# teensy.net
KiCad netlist of a schematic drawn in EAGLE
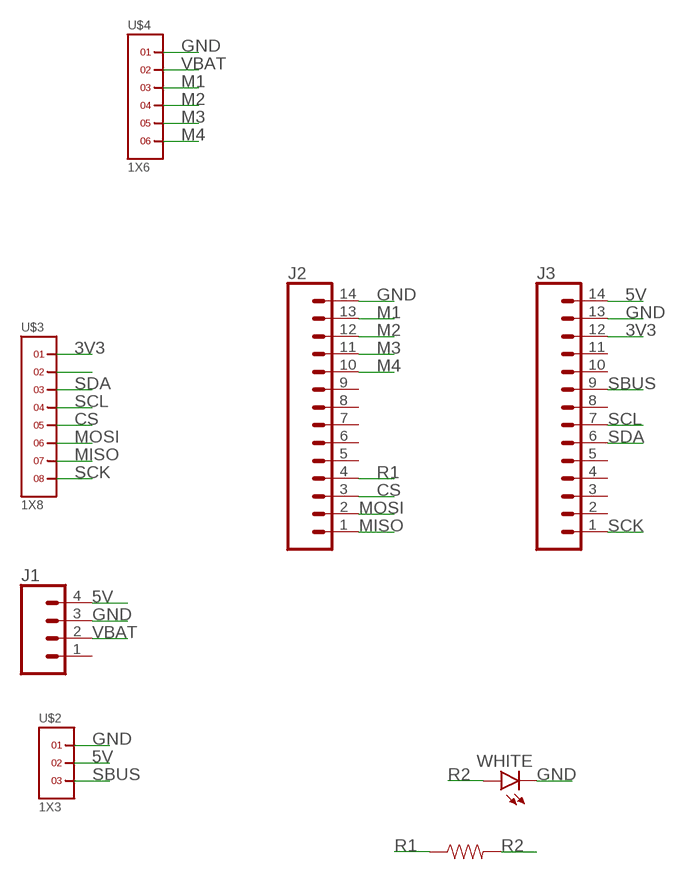
[diagram p0: schematic, sheet 1]

(export (version "E")
  (design (tool "Eeschema 10.0.6"))
  (components
    (comp (ref "D1")
      (value "WHITE")
      (footprint "eagle-import:LED-0603")
      (libsource (lib "eagle-import") (part "LED-WHITE0603"))
    )
    (comp (ref "J1")
      (value "CONN_041X04_NO_SILK")
      (footprint "eagle-import:1X04_NO_SILK")
      (libsource (lib "eagle-import") (part "CONN_041X04_NO_SILK"))
    )
    (comp (ref "J2")
      (value "CONN_14NO_SILK")
      (footprint "eagle-import:1X14_NO_SILK")
      (libsource (lib "eagle-import") (part "CONN_14NO_SILK"))
    )
    (comp (ref "J3")
      (value "CONN_14NO_SILK")
      (footprint "eagle-import:1X14_NO_SILK")
      (libsource (lib "eagle-import") (part "CONN_14NO_SILK"))
    )
    (comp (ref "R1")
      (value "22")
      (footprint "eagle-import:0603")
      (libsource (lib "eagle-import") (part "22OHM-0603-1/10W-1%"))
    )
    (comp (ref "U$2")
      (value "1X3")
      (footprint "eagle-import:1X3")
      (libsource (lib "eagle-import") (part "1X3"))
    )
    (comp (ref "U$3")
      (value "1X8")
      (footprint "eagle-import:1X8")
      (libsource (lib "eagle-import") (part "1X8"))
    )
    (comp (ref "U$4")
      (value "1X6")
      (footprint "eagle-import:1X6")
      (libsource (lib "eagle-import") (part "1X6"))
    )
  )
  (nets
    (net (code "1") (name "/3V3") (class "Default")
      (node (ref "J3") (pin "12") (pinfunction "12_12") (pintype "passive"))
      (node (ref "U$3") (pin "1") (pinfunction "1_1") (pintype "bidirectional"))
    )
    (net (code "2") (name "/5V") (class "Default")
      (node (ref "J1") (pin "4") (pinfunction "4_4") (pintype "passive"))
      (node (ref "J3") (pin "14") (pinfunction "14_14") (pintype "passive"))
      (node (ref "U$2") (pin "2") (pinfunction "2_2") (pintype "bidirectional"))
    )
    (net (code "3") (name "/CS") (class "Default")
      (node (ref "J2") (pin "3") (pinfunction "3_3") (pintype "passive"))
      (node (ref "U$3") (pin "5") (pinfunction "5_5") (pintype "bidirectional"))
    )
    (net (code "4") (name "/GND") (class "Default")
      (node (ref "D1") (pin "C") (pinfunction "C_C") (pintype "passive"))
      (node (ref "J1") (pin "3") (pinfunction "3_3") (pintype "passive"))
      (node (ref "J2") (pin "14") (pinfunction "14_14") (pintype "passive"))
      (node (ref "J3") (pin "13") (pinfunction "13_13") (pintype "passive"))
      (node (ref "U$2") (pin "1") (pinfunction "1_1") (pintype "bidirectional"))
      (node (ref "U$3") (pin "2") (pinfunction "2_2") (pintype "bidirectional"))
      (node (ref "U$4") (pin "1") (pinfunction "1_1") (pintype "bidirectional"))
    )
    (net (code "5") (name "/M1") (class "Default")
      (node (ref "J2") (pin "13") (pinfunction "13_13") (pintype "passive"))
      (node (ref "U$4") (pin "3") (pinfunction "3_3") (pintype "bidirectional"))
    )
    (net (code "6") (name "/M2") (class "Default")
      (node (ref "J2") (pin "12") (pinfunction "12_12") (pintype "passive"))
      (node (ref "U$4") (pin "4") (pinfunction "4_4") (pintype "bidirectional"))
    )
    (net (code "7") (name "/M3") (class "Default")
      (node (ref "J2") (pin "11") (pinfunction "11_11") (pintype "passive"))
      (node (ref "U$4") (pin "5") (pinfunction "5_5") (pintype "bidirectional"))
    )
    (net (code "8") (name "/M4") (class "Default")
      (node (ref "J2") (pin "10") (pinfunction "10_10") (pintype "passive"))
      (node (ref "U$4") (pin "6") (pinfunction "6_6") (pintype "bidirectional"))
    )
    (net (code "9") (name "/MISO") (class "Default")
      (node (ref "J2") (pin "1") (pinfunction "1_1") (pintype "passive"))
      (node (ref "U$3") (pin "7") (pinfunction "7_7") (pintype "bidirectional"))
    )
    (net (code "10") (name "/MOSI") (class "Default")
      (node (ref "J2") (pin "2") (pinfunction "2_2") (pintype "passive"))
      (node (ref "U$3") (pin "6") (pinfunction "6_6") (pintype "bidirectional"))
    )
    (net (code "11") (name "/R1") (class "Default")
      (node (ref "J2") (pin "4") (pinfunction "4_4") (pintype "passive"))
      (node (ref "R1") (pin "1") (pinfunction "1_1") (pintype "passive"))
    )
    (net (code "12") (name "/R2") (class "Default")
      (node (ref "D1") (pin "A") (pinfunction "A_A") (pintype "passive"))
      (node (ref "R1") (pin "2") (pinfunction "2_2") (pintype "passive"))
    )
    (net (code "13") (name "/SBUS") (class "Default")
      (node (ref "J3") (pin "9") (pinfunction "9_9") (pintype "passive"))
      (node (ref "U$2") (pin "3") (pinfunction "3_3") (pintype "bidirectional"))
    )
    (net (code "14") (name "/SCK") (class "Default")
      (node (ref "J3") (pin "1") (pinfunction "1_1") (pintype "passive"))
      (node (ref "U$3") (pin "8") (pinfunction "8_8") (pintype "bidirectional"))
    )
    (net (code "15") (name "/SCL") (class "Default")
      (node (ref "J3") (pin "7") (pinfunction "7_7") (pintype "passive"))
      (node (ref "U$3") (pin "4") (pinfunction "4_4") (pintype "bidirectional"))
    )
    (net (code "16") (name "/SDA") (class "Default")
      (node (ref "J3") (pin "6") (pinfunction "6_6") (pintype "passive"))
      (node (ref "U$3") (pin "3") (pinfunction "3_3") (pintype "bidirectional"))
    )
    (net (code "17") (name "/VBAT") (class "Default")
      (node (ref "J1") (pin "2") (pinfunction "2_2") (pintype "passive"))
      (node (ref "U$4") (pin "2") (pinfunction "2_2") (pintype "bidirectional"))
    )
    (net (code "18") (name "unconnected-(J1-Pad1)") (class "Default")
      (node (ref "J1") (pin "1") (pinfunction "1_1") (pintype "passive"))
    )
    (net (code "19") (name "unconnected-(J2-Pad5)") (class "Default")
      (node (ref "J2") (pin "5") (pinfunction "5_5") (pintype "passive"))
    )
    (net (code "20") (name "unconnected-(J2-Pad6)") (class "Default")
      (node (ref "J2") (pin "6") (pinfunction "6_6") (pintype "passive"))
    )
    (net (code "21") (name "unconnected-(J2-Pad7)") (class "Default")
      (node (ref "J2") (pin "7") (pinfunction "7_7") (pintype "passive"))
    )
    (net (code "22") (name "unconnected-(J2-Pad8)") (class "Default")
      (node (ref "J2") (pin "8") (pinfunction "8_8") (pintype "passive"))
    )
    (net (code "23") (name "unconnected-(J2-Pad9)") (class "Default")
      (node (ref "J2") (pin "9") (pinfunction "9_9") (pintype "passive"))
    )
    (net (code "24") (name "unconnected-(J3-Pad2)") (class "Default")
      (node (ref "J3") (pin "2") (pinfunction "2_2") (pintype "passive"))
    )
    (net (code "25") (name "unconnected-(J3-Pad3)") (class "Default")
      (node (ref "J3") (pin "3") (pinfunction "3_3") (pintype "passive"))
    )
    (net (code "26") (name "unconnected-(J3-Pad4)") (class "Default")
      (node (ref "J3") (pin "4") (pinfunction "4_4") (pintype "passive"))
    )
    (net (code "27") (name "unconnected-(J3-Pad5)") (class "Default")
      (node (ref "J3") (pin "5") (pinfunction "5_5") (pintype "passive"))
    )
    (net (code "28") (name "unconnected-(J3-Pad8)") (class "Default")
      (node (ref "J3") (pin "8") (pinfunction "8_8") (pintype "passive"))
    )
    (net (code "29") (name "unconnected-(J3-Pad10)") (class "Default")
      (node (ref "J3") (pin "10") (pinfunction "10_10") (pintype "passive"))
    )
    (net (code "30") (name "unconnected-(J3-Pad11)") (class "Default")
      (node (ref "J3") (pin "11") (pinfunction "11_11") (pintype "passive"))
    )
  )
)
